# key_diy_btm_wider.net
KiCad netlist of a schematic drawn in EAGLE
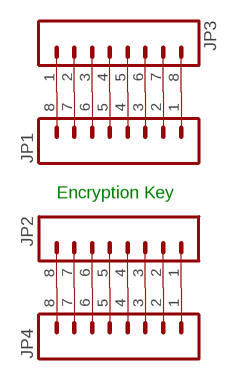
[diagram p0: schematic, sheet 1]

(export (version "E")
  (design (tool "Eeschema 10.0.6"))
  (components
    (comp (ref "JP1")
      (value "M08LOCK")
      (footprint "eagle-import:1X08_LOCK")
      (libsource (lib "eagle-import") (part "M08LOCK"))
    )
    (comp (ref "JP2")
      (value "M08LOCK")
      (footprint "eagle-import:1X08_LOCK")
      (libsource (lib "eagle-import") (part "M08LOCK"))
    )
    (comp (ref "JP3")
      (value "M08LONGPADS")
      (footprint "eagle-import:1X08_LONGPADS")
      (libsource (lib "eagle-import") (part "M08LONGPADS"))
    )
    (comp (ref "JP4")
      (value "M08LONGPADS")
      (footprint "eagle-import:1X08_LONGPADS")
      (libsource (lib "eagle-import") (part "M08LONGPADS"))
    )
  )
  (nets
    (net (code "1") (name "Net-(JP1-Pad1)") (class "Default")
      (node (ref "JP1") (pin "1") (pinfunction "1_1") (pintype "passive"))
      (node (ref "JP3") (pin "8") (pinfunction "8_8") (pintype "passive"))
    )
    (net (code "2") (name "Net-(JP1-Pad2)") (class "Default")
      (node (ref "JP1") (pin "2") (pinfunction "2_2") (pintype "passive"))
      (node (ref "JP3") (pin "7") (pinfunction "7_7") (pintype "passive"))
    )
    (net (code "3") (name "Net-(JP1-Pad3)") (class "Default")
      (node (ref "JP1") (pin "3") (pinfunction "3_3") (pintype "passive"))
      (node (ref "JP3") (pin "6") (pinfunction "6_6") (pintype "passive"))
    )
    (net (code "4") (name "Net-(JP1-Pad4)") (class "Default")
      (node (ref "JP1") (pin "4") (pinfunction "4_4") (pintype "passive"))
      (node (ref "JP3") (pin "5") (pinfunction "5_5") (pintype "passive"))
    )
    (net (code "5") (name "Net-(JP1-Pad5)") (class "Default")
      (node (ref "JP1") (pin "5") (pinfunction "5_5") (pintype "passive"))
      (node (ref "JP3") (pin "4") (pinfunction "4_4") (pintype "passive"))
    )
    (net (code "6") (name "Net-(JP1-Pad6)") (class "Default")
      (node (ref "JP1") (pin "6") (pinfunction "6_6") (pintype "passive"))
      (node (ref "JP3") (pin "3") (pinfunction "3_3") (pintype "passive"))
    )
    (net (code "7") (name "Net-(JP1-Pad7)") (class "Default")
      (node (ref "JP1") (pin "7") (pinfunction "7_7") (pintype "passive"))
      (node (ref "JP3") (pin "2") (pinfunction "2_2") (pintype "passive"))
    )
    (net (code "8") (name "Net-(JP1-Pad8)") (class "Default")
      (node (ref "JP1") (pin "8") (pinfunction "8_8") (pintype "passive"))
      (node (ref "JP3") (pin "1") (pinfunction "1_1") (pintype "passive"))
    )
    (net (code "9") (name "Net-(JP2-Pad1)") (class "Default")
      (node (ref "JP2") (pin "1") (pinfunction "1_1") (pintype "passive"))
      (node (ref "JP4") (pin "1") (pinfunction "1_1") (pintype "passive"))
    )
    (net (code "10") (name "Net-(JP2-Pad2)") (class "Default")
      (node (ref "JP2") (pin "2") (pinfunction "2_2") (pintype "passive"))
      (node (ref "JP4") (pin "2") (pinfunction "2_2") (pintype "passive"))
    )
    (net (code "11") (name "Net-(JP2-Pad3)") (class "Default")
      (node (ref "JP2") (pin "3") (pinfunction "3_3") (pintype "passive"))
      (node (ref "JP4") (pin "3") (pinfunction "3_3") (pintype "passive"))
    )
    (net (code "12") (name "Net-(JP2-Pad4)") (class "Default")
      (node (ref "JP2") (pin "4") (pinfunction "4_4") (pintype "passive"))
      (node (ref "JP4") (pin "4") (pinfunction "4_4") (pintype "passive"))
    )
    (net (code "13") (name "Net-(JP2-Pad5)") (class "Default")
      (node (ref "JP2") (pin "5") (pinfunction "5_5") (pintype "passive"))
      (node (ref "JP4") (pin "5") (pinfunction "5_5") (pintype "passive"))
    )
    (net (code "14") (name "Net-(JP2-Pad6)") (class "Default")
      (node (ref "JP2") (pin "6") (pinfunction "6_6") (pintype "passive"))
      (node (ref "JP4") (pin "6") (pinfunction "6_6") (pintype "passive"))
    )
    (net (code "15") (name "Net-(JP2-Pad7)") (class "Default")
      (node (ref "JP2") (pin "7") (pinfunction "7_7") (pintype "passive"))
      (node (ref "JP4") (pin "7") (pinfunction "7_7") (pintype "passive"))
    )
    (net (code "16") (name "Net-(JP2-Pad8)") (class "Default")
      (node (ref "JP2") (pin "8") (pinfunction "8_8") (pintype "passive"))
      (node (ref "JP4") (pin "8") (pinfunction "8_8") (pintype "passive"))
    )
  )
)
